# C64_KernalSw_16k.net
KiCad netlist of a schematic drawn in EAGLE
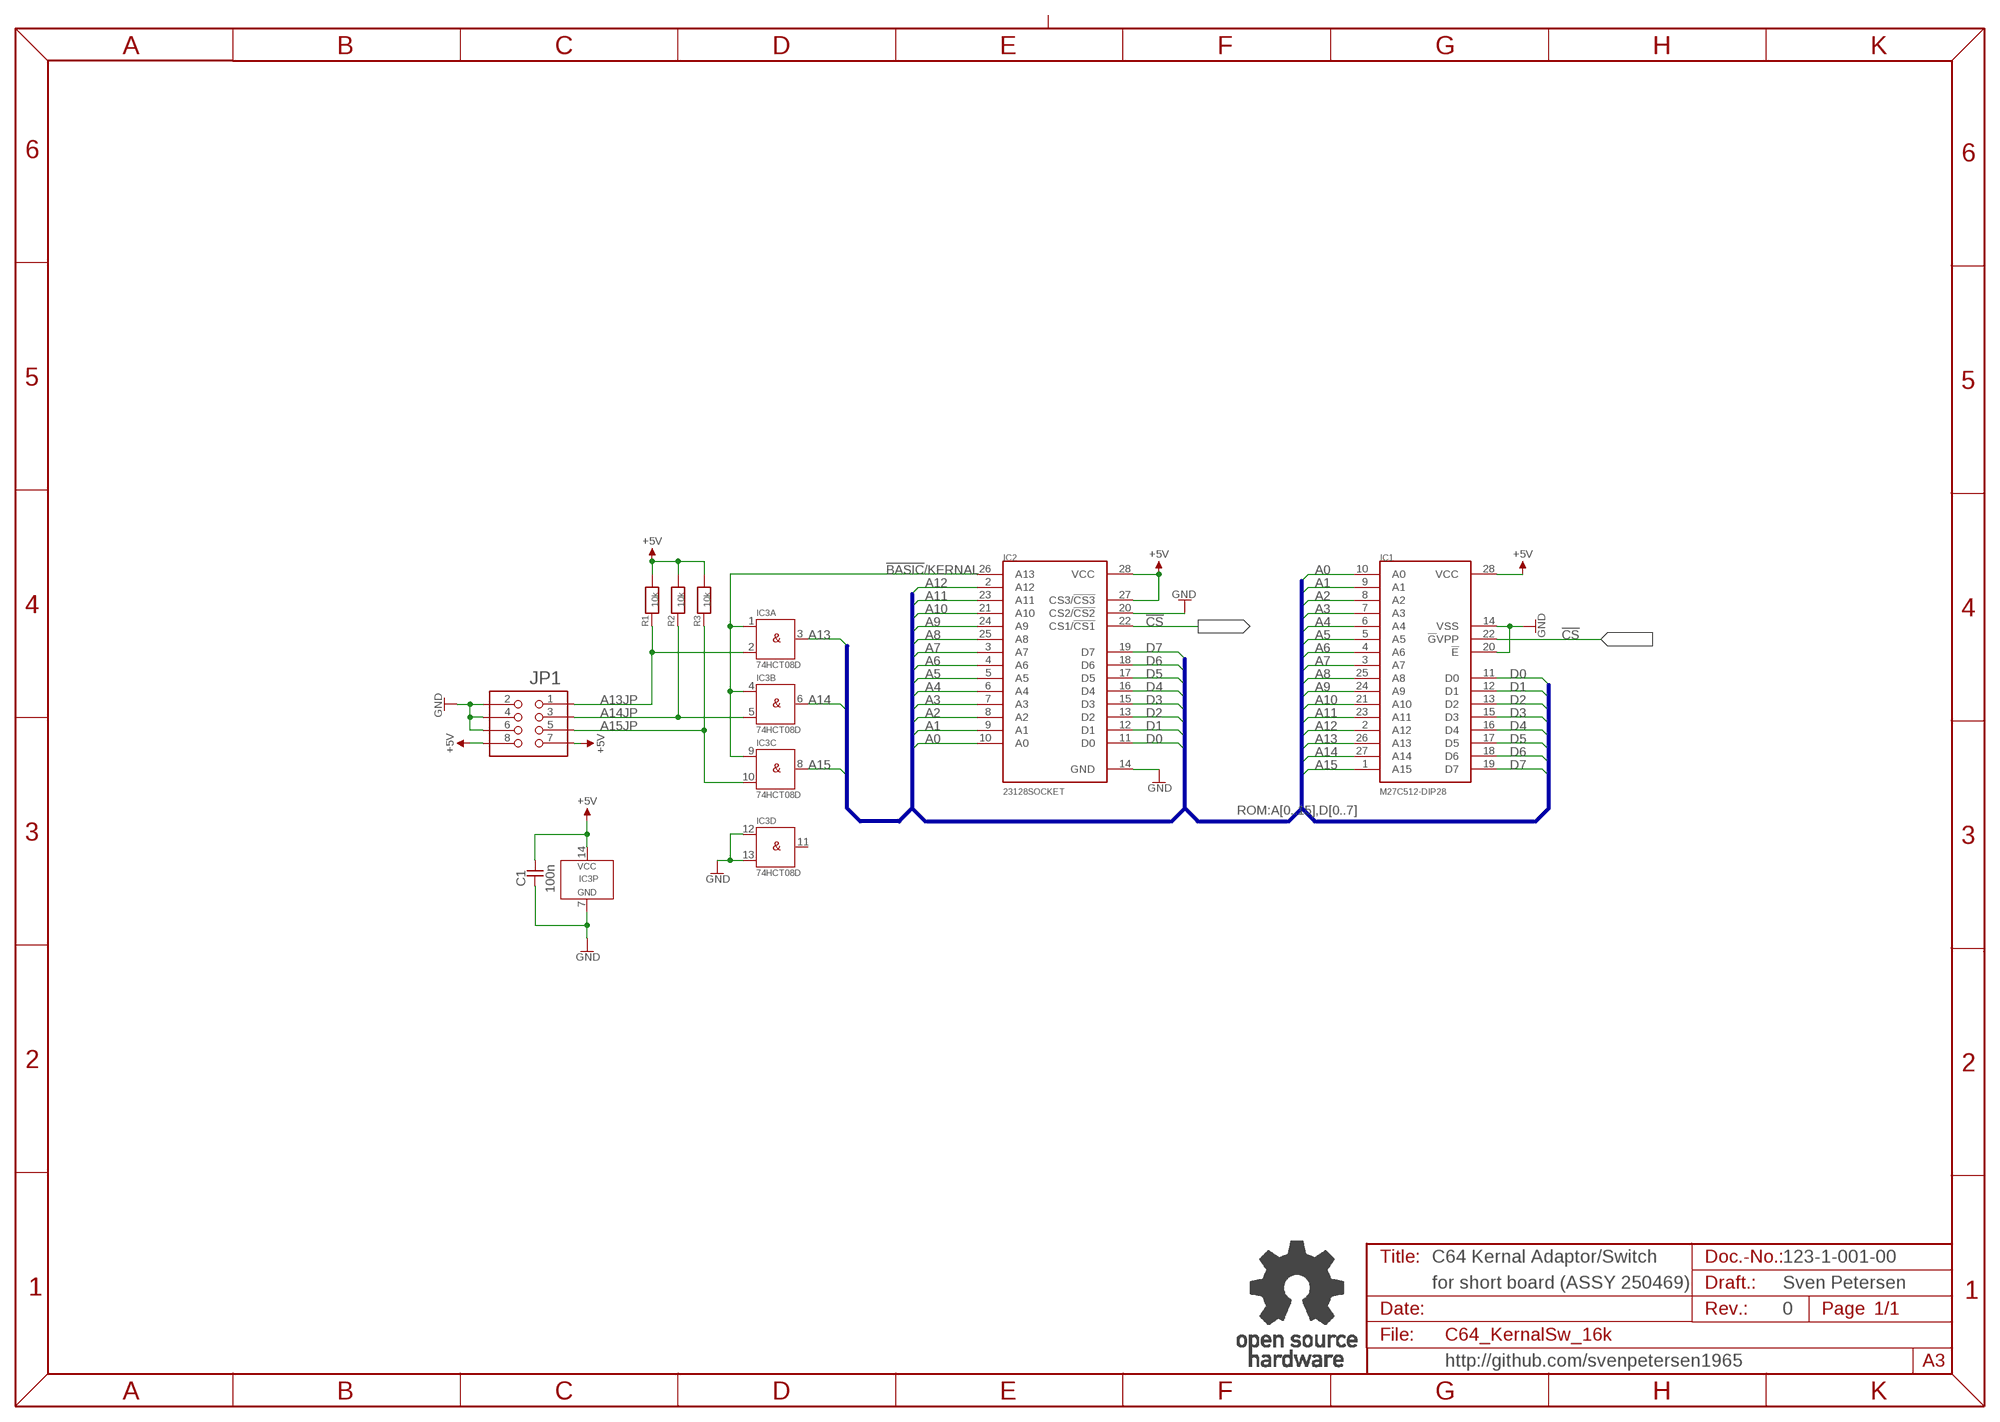
[diagram p0: schematic, sheet 1]

(export (version "E")
  (design (tool "Eeschema 10.0.6"))
  (components
    (comp (ref "C1")
      (value "100n")
      (footprint "eagle-import:0805")
      (libsource (lib "eagle-import") (part "C-0805"))
    )
    (comp (ref "IC1")
      (value "M27C512-DIP28")
      (footprint "eagle-import:DIL28-6")
      (libsource (lib "eagle-import") (part "M27C512-DIP28"))
    )
    (comp (ref "IC2")
      (value "23128SOCKET")
      (footprint "eagle-import:DIL28_SOCKET")
      (libsource (lib "eagle-import") (part "23128SOCKET"))
    )
    (comp (ref "IC3")
      (value "74HCT08D")
      (footprint "eagle-import:SO-14")
      (libsource (lib "eagle-import") (part "7408HC"))
    )
    (comp (ref "JP1")
      (value "PINHD-2X490°/MPE_088")
      (footprint "eagle-import:2X04_90_SERIES_088")
      (libsource (lib "eagle-import") (part "PINHD-2X490°/MPE_088"))
    )
    (comp (ref "R1")
      (value "10k")
      (footprint "eagle-import:0805")
      (libsource (lib "eagle-import") (part "R-0805"))
    )
    (comp (ref "R2")
      (value "10k")
      (footprint "eagle-import:0805")
      (libsource (lib "eagle-import") (part "R-0805"))
    )
    (comp (ref "R3")
      (value "10k")
      (footprint "eagle-import:0805")
      (libsource (lib "eagle-import") (part "R-0805"))
    )
    (comp (ref "U$21")
      (value "OPEN_SOURCE_HW")
      (footprint "eagle-import:OPENHW")
      (libsource (lib "eagle-import") (part "OPEN_SOURCE_HW"))
    )
  )
  (nets
    (net (code "1") (name "+5V") (class "Default")
      (node (ref "C1") (pin "2") (pinfunction "2_2") (pintype "passive"))
      (node (ref "IC1") (pin "28") (pinfunction "VCC_28") (pintype "power_in"))
      (node (ref "IC2") (pin "27") (pinfunction "CS3/~{CS3}_27") (pintype "input"))
      (node (ref "IC2") (pin "28") (pinfunction "VCC_28") (pintype "power_in"))
      (node (ref "IC3") (pin "14") (pinfunction "VCC_14") (pintype "bidirectional"))
      (node (ref "JP1") (pin "7") (pinfunction "7_7") (pintype "passive"))
      (node (ref "JP1") (pin "8") (pinfunction "8_8") (pintype "passive"))
      (node (ref "R1") (pin "2") (pinfunction "2_2") (pintype "passive"))
      (node (ref "R2") (pin "2") (pinfunction "2_2") (pintype "passive"))
      (node (ref "R3") (pin "2") (pinfunction "2_2") (pintype "passive"))
    )
    (net (code "2") (name "/A0") (class "Default")
      (node (ref "IC1") (pin "10") (pinfunction "A0_10") (pintype "input"))
      (node (ref "IC2") (pin "10") (pinfunction "A0_10") (pintype "input"))
    )
    (net (code "3") (name "/A1") (class "Default")
      (node (ref "IC1") (pin "9") (pinfunction "A1_9") (pintype "input"))
      (node (ref "IC2") (pin "9") (pinfunction "A1_9") (pintype "input"))
    )
    (net (code "4") (name "/A2") (class "Default")
      (node (ref "IC1") (pin "8") (pinfunction "A2_8") (pintype "input"))
      (node (ref "IC2") (pin "8") (pinfunction "A2_8") (pintype "input"))
    )
    (net (code "5") (name "/A3") (class "Default")
      (node (ref "IC1") (pin "7") (pinfunction "A3_7") (pintype "input"))
      (node (ref "IC2") (pin "7") (pinfunction "A3_7") (pintype "input"))
    )
    (net (code "6") (name "/A4") (class "Default")
      (node (ref "IC1") (pin "6") (pinfunction "A4_6") (pintype "input"))
      (node (ref "IC2") (pin "6") (pinfunction "A4_6") (pintype "input"))
    )
    (net (code "7") (name "/A5") (class "Default")
      (node (ref "IC1") (pin "5") (pinfunction "A5_5") (pintype "input"))
      (node (ref "IC2") (pin "5") (pinfunction "A5_5") (pintype "input"))
    )
    (net (code "8") (name "/A6") (class "Default")
      (node (ref "IC1") (pin "4") (pinfunction "A6_4") (pintype "input"))
      (node (ref "IC2") (pin "4") (pinfunction "A6_4") (pintype "input"))
    )
    (net (code "9") (name "/A7") (class "Default")
      (node (ref "IC1") (pin "3") (pinfunction "A7_3") (pintype "input"))
      (node (ref "IC2") (pin "3") (pinfunction "A7_3") (pintype "input"))
    )
    (net (code "10") (name "/A8") (class "Default")
      (node (ref "IC1") (pin "25") (pinfunction "A8_25") (pintype "input"))
      (node (ref "IC2") (pin "25") (pinfunction "A8_25") (pintype "input"))
    )
    (net (code "11") (name "/A9") (class "Default")
      (node (ref "IC1") (pin "24") (pinfunction "A9_24") (pintype "input"))
      (node (ref "IC2") (pin "24") (pinfunction "A9_24") (pintype "input"))
    )
    (net (code "12") (name "/A10") (class "Default")
      (node (ref "IC1") (pin "21") (pinfunction "A10_21") (pintype "input"))
      (node (ref "IC2") (pin "21") (pinfunction "A10_21") (pintype "input"))
    )
    (net (code "13") (name "/A11") (class "Default")
      (node (ref "IC1") (pin "23") (pinfunction "A11_23") (pintype "input"))
      (node (ref "IC2") (pin "23") (pinfunction "A11_23") (pintype "input"))
    )
    (net (code "14") (name "/A12") (class "Default")
      (node (ref "IC1") (pin "2") (pinfunction "A12_2") (pintype "input"))
      (node (ref "IC2") (pin "2") (pinfunction "A12_2") (pintype "input"))
    )
    (net (code "15") (name "/A13") (class "Default")
      (node (ref "IC1") (pin "26") (pinfunction "A13_26") (pintype "input"))
      (node (ref "IC3") (pin "3") (pinfunction "O_3") (pintype "output"))
    )
    (net (code "16") (name "/A13JP") (class "Default")
      (node (ref "IC3") (pin "2") (pinfunction "I1_2") (pintype "input"))
      (node (ref "JP1") (pin "1") (pinfunction "1_1") (pintype "passive"))
      (node (ref "R1") (pin "1") (pinfunction "1_1") (pintype "passive"))
    )
    (net (code "17") (name "/A14") (class "Default")
      (node (ref "IC1") (pin "27") (pinfunction "A14_27") (pintype "input"))
      (node (ref "IC3") (pin "6") (pinfunction "O_6") (pintype "output"))
    )
    (net (code "18") (name "/A14JP") (class "Default")
      (node (ref "IC3") (pin "5") (pinfunction "I1_5") (pintype "input"))
      (node (ref "JP1") (pin "3") (pinfunction "3_3") (pintype "passive"))
      (node (ref "R2") (pin "1") (pinfunction "1_1") (pintype "passive"))
    )
    (net (code "19") (name "/A15") (class "Default")
      (node (ref "IC1") (pin "1") (pinfunction "A15_1") (pintype "input"))
      (node (ref "IC3") (pin "8") (pinfunction "O_8") (pintype "output"))
    )
    (net (code "20") (name "/A15JP") (class "Default")
      (node (ref "IC3") (pin "10") (pinfunction "I1_10") (pintype "input"))
      (node (ref "JP1") (pin "5") (pinfunction "5_5") (pintype "passive"))
      (node (ref "R3") (pin "1") (pinfunction "1_1") (pintype "passive"))
    )
    (net (code "21") (name "/D0") (class "Default")
      (node (ref "IC1") (pin "11") (pinfunction "D0_11") (pintype "bidirectional"))
      (node (ref "IC2") (pin "11") (pinfunction "D0_11") (pintype "tri_state"))
    )
    (net (code "22") (name "/D1") (class "Default")
      (node (ref "IC1") (pin "12") (pinfunction "D1_12") (pintype "bidirectional"))
      (node (ref "IC2") (pin "12") (pinfunction "D1_12") (pintype "tri_state"))
    )
    (net (code "23") (name "/D2") (class "Default")
      (node (ref "IC1") (pin "13") (pinfunction "D2_13") (pintype "bidirectional"))
      (node (ref "IC2") (pin "13") (pinfunction "D2_13") (pintype "tri_state"))
    )
    (net (code "24") (name "/D3") (class "Default")
      (node (ref "IC1") (pin "15") (pinfunction "D3_15") (pintype "bidirectional"))
      (node (ref "IC2") (pin "15") (pinfunction "D3_15") (pintype "tri_state"))
    )
    (net (code "25") (name "/D4") (class "Default")
      (node (ref "IC1") (pin "16") (pinfunction "D4_16") (pintype "bidirectional"))
      (node (ref "IC2") (pin "16") (pinfunction "D4_16") (pintype "tri_state"))
    )
    (net (code "26") (name "/D5") (class "Default")
      (node (ref "IC1") (pin "17") (pinfunction "D5_17") (pintype "bidirectional"))
      (node (ref "IC2") (pin "17") (pinfunction "D5_17") (pintype "tri_state"))
    )
    (net (code "27") (name "/D6") (class "Default")
      (node (ref "IC1") (pin "18") (pinfunction "D6_18") (pintype "bidirectional"))
      (node (ref "IC2") (pin "18") (pinfunction "D6_18") (pintype "tri_state"))
    )
    (net (code "28") (name "/D7") (class "Default")
      (node (ref "IC1") (pin "19") (pinfunction "D7_19") (pintype "bidirectional"))
      (node (ref "IC2") (pin "19") (pinfunction "D7_19") (pintype "tri_state"))
    )
    (net (code "30") (name "/~{BASIC}{slash}KERNAL") (class "Default")
      (node (ref "IC2") (pin "26") (pinfunction "A13_26") (pintype "input"))
      (node (ref "IC3") (pin "1") (pinfunction "I0_1") (pintype "input"))
      (node (ref "IC3") (pin "4") (pinfunction "I0_4") (pintype "input"))
      (node (ref "IC3") (pin "9") (pinfunction "I0_9") (pintype "input"))
    )
    (net (code "31") (name "/~{CS}") (class "Default")
      (node (ref "IC1") (pin "22") (pinfunction "~{G}VPP_22") (pintype "input"))
      (node (ref "IC2") (pin "22") (pinfunction "CS1/~{CS1}_22") (pintype "input"))
    )
    (net (code "32") (name "GND") (class "Default")
      (node (ref "C1") (pin "1") (pinfunction "1_1") (pintype "passive"))
      (node (ref "IC1") (pin "14") (pinfunction "VSS_14") (pintype "power_in"))
      (node (ref "IC1") (pin "20") (pinfunction "~{E}_20") (pintype "input"))
      (node (ref "IC2") (pin "14") (pinfunction "GND_14") (pintype "power_in"))
      (node (ref "IC2") (pin "20") (pinfunction "CS2/~{CS2}_20") (pintype "input"))
      (node (ref "IC3") (pin "12") (pinfunction "I0_12") (pintype "input"))
      (node (ref "IC3") (pin "13") (pinfunction "I1_13") (pintype "input"))
      (node (ref "IC3") (pin "7") (pinfunction "GND_7") (pintype "bidirectional"))
      (node (ref "JP1") (pin "2") (pinfunction "2_2") (pintype "passive"))
      (node (ref "JP1") (pin "4") (pinfunction "4_4") (pintype "passive"))
      (node (ref "JP1") (pin "6") (pinfunction "6_6") (pintype "passive"))
    )
    (net (code "33") (name "unconnected-(IC3D-O-Pad11)") (class "Default")
      (node (ref "IC3") (pin "11") (pinfunction "O_11") (pintype "output"))
    )
  )
)
